# MMC-MAG.net
KiCad netlist of a schematic drawn in Altium Designer
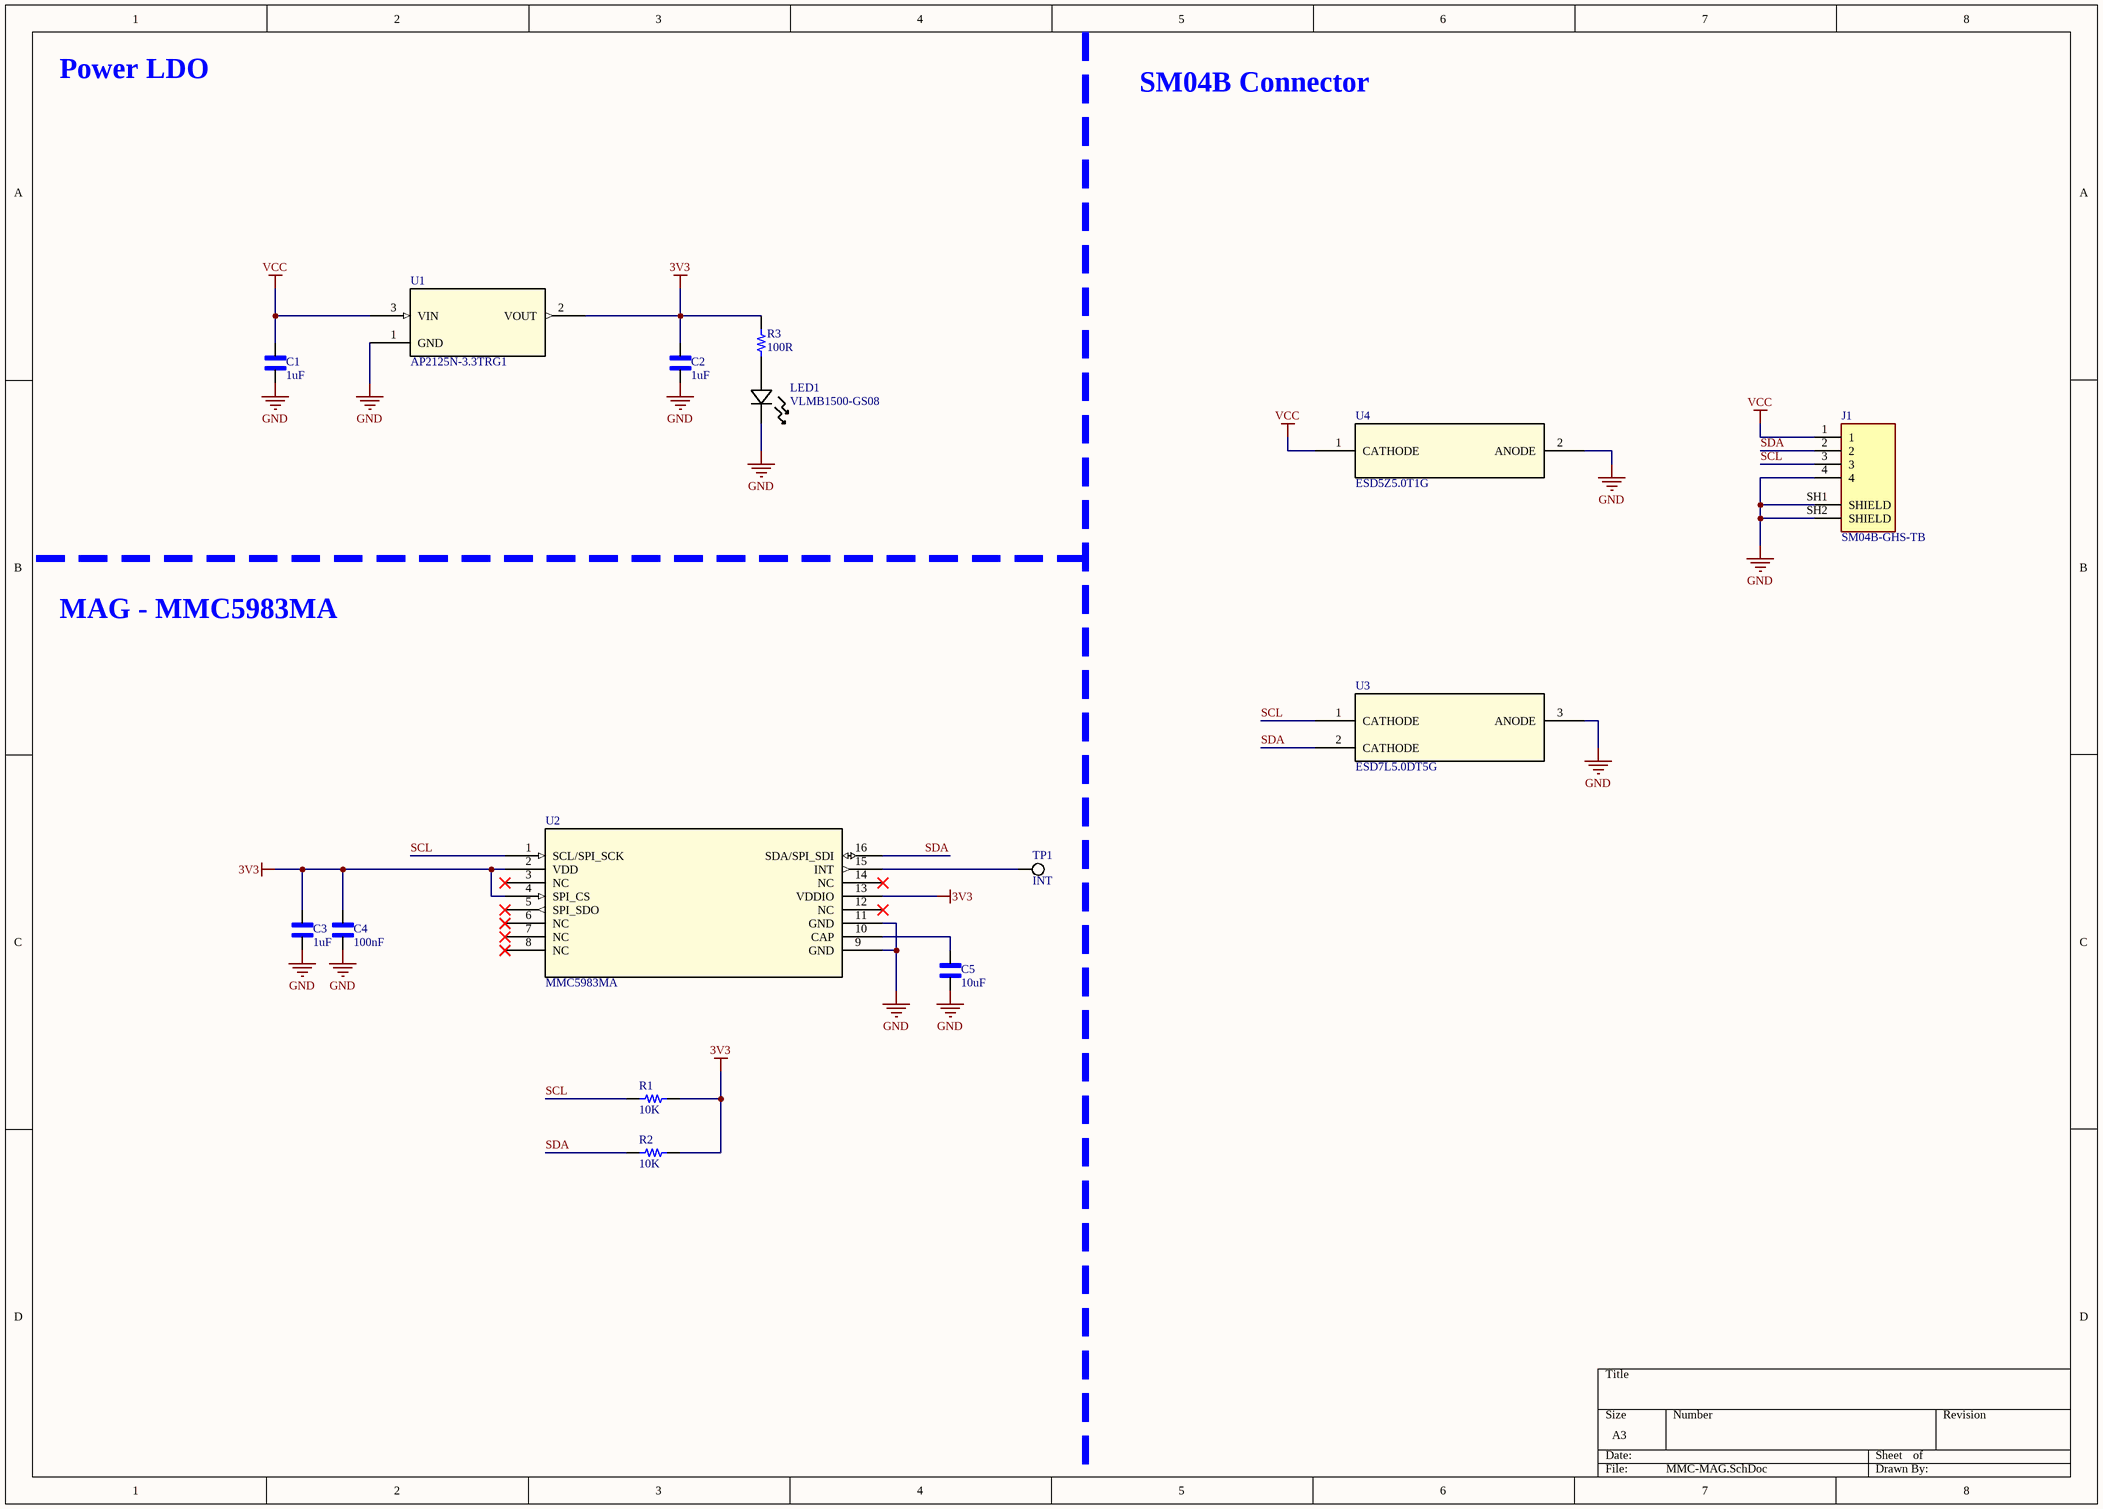
[diagram p0: MMC-MAG.SchDoc]

(export (version "E")
  (design (tool "Eeschema 10.0.6"))
  (components
    (comp (ref "C1")
      (value "1uF")
      (footprint "CAP0402")
      (description "1 ÂµF Â±10% 25V Ceramic Capacitor X5R 0402 (1005 Metric)")
      (fields (field (name "MF") "Murata") (field (name "MPN") "GRM155R61E105KA12D"))
      (libsource (lib "MAG-Schlib") (part "GRM155R61E105KA12D"))
    )
    (comp (ref "C2")
      (value "1uF")
      (footprint "CAP0402")
      (description "1 ÂµF Â±10% 25V Ceramic Capacitor X5R 0402 (1005 Metric)")
      (fields (field (name "MF") "Murata") (field (name "MPN") "GRM155R61E105KA12D"))
      (libsource (lib "MAG-Schlib") (part "GRM155R61E105KA12D"))
    )
    (comp (ref "C3")
      (value "1uF")
      (footprint "CAP0402")
      (description "1 ÂµF Â±10% 25V Ceramic Capacitor X5R 0402 (1005 Metric)")
      (fields (field (name "MF") "Murata") (field (name "MPN") "GRM155R61E105KA12D"))
      (libsource (lib "MAG-Schlib") (part "GRM155R61E105KA12D"))
    )
    (comp (ref "C4")
      (value "100nF")
      (footprint "CAP0402")
      (description "Ceramic Capacitor, Ceramic, 10V, 10% +Tol, 10% -Tol, X5R, 15% TC, 0.1uF, Surface Mount, 0402")
      (fields
        (field (name "MANUFACTURER") "Murata")
        (field (name "MANUFACTURER PART NUMBER") "GRM155R61A104KA01D")
      )
      (libsource (lib "MAG-Schlib") (part "GRM155R61A104KA01D"))
    )
    (comp (ref "C5")
      (value "10uF")
      (footprint "CAP0402")
      (description "Ceramic Capacitor, Ceramic, 10V, 20% +Tol, 20% -Tol, X5R, 15% TC, 10uF, Surface Mount, 0402")
      (fields
        (field (name "MANUFACTURER") "Murata")
        (field (name "MANUFACTURER PART NUMBER") "GRM155R61A106ME11D")
      )
      (libsource (lib "MAG-Schlib") (part "GRM155R61A106ME11D"))
    )
    (comp (ref "J1")
      (value "SM04B-GHS-TB")
      (footprint "JST_SM04B-GHS-TB(LF)(SN)-")
      (description "Connector Header Surface Mount, Right Angle 4 position 0.049 (1.25mm)")
      (fields (field (name "MF") "JST Sales America Inc.") (field (name "MPN") "SM04B-GHS-TB(LF)(SN)"))
      (libsource (lib "MAG-Schlib") (part "SM04B-GHS-TB(LF)(SN)-"))
    )
    (comp (ref "LED1")
      (value "VLMB1500-GS08")
      (footprint "LED_500-GS08_VIS")
      (description "CHIPLED(0402) BLUE ULTRABRIGHT -e4")
      (fields (field (name "COPYRIGHT") "Copyright (C) 2025 Ultra Librarian. All rights reserved."))
      (libsource (lib "MAG-Schlib") (part "VLMB1500-GS08"))
    )
    (comp (ref "R1")
      (value "10K")
      (footprint "RES 0402_1005")
      (description "Res Thick Film 0402 10K Ohm 5% 0.063W(1/16W) ±100ppm/C Pad SMD T/R")
      (fields
        (field (name "MANUFACTURER") "Yageo Group")
        (field (name "MANUFACTURER PART NUMBER") "RC0402JR-0710KL")
      )
      (libsource (lib "MAG-Schlib") (part "RC0402JR-0710KL"))
    )
    (comp (ref "R2")
      (value "10K")
      (footprint "RES 0402_1005")
      (description "Res Thick Film 0402 10K Ohm 5% 0.063W(1/16W) ±100ppm/C Pad SMD T/R")
      (fields
        (field (name "MANUFACTURER") "Yageo Group")
        (field (name "MANUFACTURER PART NUMBER") "RC0402JR-0710KL")
      )
      (libsource (lib "MAG-Schlib") (part "RC0402JR-0710KL"))
    )
    (comp (ref "R3")
      (value "100R")
      (footprint "RES 0402_1005")
      (description "Res Thick Film 0402 100 Ohm 1% 0.2W ±100ppm/°C Molded SMD SMD Paper T/R")
      (fields
        (field (name "MANUFACTURER") "Vishay")
        (field (name "MANUFACTURER PART NUMBER") "CRCW0402100RFKEDHP")
      )
      (libsource (lib "MAG-Schlib") (part "CRCW0402100RFKEDHP"))
    )
    (comp (ref "TP1")
      (value "INT")
      (footprint "TEST_POINT")
      (libsource (lib "MAG-Schlib") (part "TEST_POINT"))
    )
    (comp (ref "U1")
      (value "AP2125N-3.3TRG1")
      (footprint "SOT-23_DIO")
      (description "IC REG LINEAR 3.3V 300MA SOT23-3")
      (fields (field (name "COPYRIGHT") "Copyright (C) 2025 Ultra Librarian. All rights reserved."))
      (libsource (lib "MAG-Schlib") (part "AP2125N-3.3TRG1"))
    )
    (comp (ref "U2")
      (value "MMC5983MA")
      (footprint "MMC5983MA_MEM")
      (description "3-AXIS MAGNETIC SENSOR")
      (fields (field (name "COPYRIGHT") "Copyright (C) 2025 Ultra Librarian. All rights reserved."))
      (libsource (lib "MMC5983MA") (part "MMC5983MA"))
    )
    (comp (ref "U3")
      (value "ESD7L5.0DT5G")
      (footprint "SOT-723_0P85X1P25_ONS")
      (description "TVS DIODE 5VWM 10.4VC SOT723")
      (fields (field (name "COPYRIGHT") "Copyright (C) 2025 Ultra Librarian. All rights reserved."))
      (libsource (lib "ESD7L5P0DT5G") (part "ESD7L5.0DT5G"))
    )
    (comp (ref "U4")
      (value "ESD5Z5.0T1G")
      (footprint "SOD-523_0P9X1P3_ONS")
      (description "TVS DIODE 5VWM 18.6VC SOD523")
      (fields (field (name "COPYRIGHT") "Copyright (C) 2025 Ultra Librarian. All rights reserved."))
      (libsource (lib "MAG-Schlib") (part "ESD5Z5.0T1G"))
    )
  )
  (nets
    (net (code "1") (name "/SCL") (class "Default")
      (node (ref "J1") (pin "3") (pinfunction "3_3") (pintype "passive"))
      (node (ref "R1") (pin "1") (pinfunction "1_1") (pintype "passive"))
      (node (ref "U2") (pin "1") (pinfunction "SCL/SPI_SCK_1") (pintype "input"))
      (node (ref "U3") (pin "1") (pinfunction "CATHODE_1") (pintype "passive"))
    )
    (net (code "2") (name "/SDA") (class "Default")
      (node (ref "J1") (pin "2") (pinfunction "2_2") (pintype "passive"))
      (node (ref "R2") (pin "2") (pinfunction "2_2") (pintype "passive"))
      (node (ref "U2") (pin "16") (pinfunction "SDA/SPI_SDI_16") (pintype "bidirectional"))
      (node (ref "U3") (pin "2") (pinfunction "CATHODE_2") (pintype "passive"))
    )
    (net (code "3") (name "3V3") (class "Default")
      (node (ref "C2") (pin "2") (pinfunction "2_2") (pintype "passive"))
      (node (ref "C3") (pin "2") (pinfunction "2_2") (pintype "passive"))
      (node (ref "C4") (pin "2") (pinfunction "2_2") (pintype "passive"))
      (node (ref "R1") (pin "2") (pinfunction "2_2") (pintype "passive"))
      (node (ref "R2") (pin "1") (pinfunction "1_1") (pintype "passive"))
      (node (ref "R3") (pin "2") (pinfunction "2_2") (pintype "passive"))
      (node (ref "U1") (pin "2") (pinfunction "VOUT_2") (pintype "output"))
      (node (ref "U2") (pin "13") (pinfunction "VDDIO_13") (pintype "power_in"))
      (node (ref "U2") (pin "2") (pinfunction "VDD_2") (pintype "power_in"))
      (node (ref "U2") (pin "4") (pinfunction "SPI_CS_4") (pintype "input"))
    )
    (net (code "4") (name "GND") (class "Default")
      (node (ref "C1") (pin "1") (pinfunction "1_1") (pintype "passive"))
      (node (ref "C2") (pin "1") (pinfunction "1_1") (pintype "passive"))
      (node (ref "C3") (pin "1") (pinfunction "1_1") (pintype "passive"))
      (node (ref "C4") (pin "1") (pinfunction "1_1") (pintype "passive"))
      (node (ref "C5") (pin "1") (pinfunction "1_1") (pintype "passive"))
      (node (ref "J1") (pin "4") (pinfunction "4_4") (pintype "passive"))
      (node (ref "J1") (pin "SH1") (pinfunction "SHIELD_SH1") (pintype "power_in"))
      (node (ref "J1") (pin "SH2") (pinfunction "SHIELD_SH2") (pintype "power_in"))
      (node (ref "LED1") (pin "1") (pinfunction "1_1") (pintype "passive"))
      (node (ref "U1") (pin "1") (pinfunction "GND_1") (pintype "power_in"))
      (node (ref "U2") (pin "11") (pinfunction "GND_11") (pintype "power_in"))
      (node (ref "U2") (pin "9") (pinfunction "GND_9") (pintype "power_in"))
      (node (ref "U3") (pin "3") (pinfunction "ANODE_3") (pintype "passive"))
      (node (ref "U4") (pin "2") (pinfunction "ANODE_2") (pintype "passive"))
    )
    (net (code "5") (name "Net-(LED1-Pad2)") (class "Default")
      (node (ref "LED1") (pin "2") (pinfunction "2_2") (pintype "passive"))
      (node (ref "R3") (pin "1") (pinfunction "1_1") (pintype "passive"))
    )
    (net (code "6") (name "Net-(U2-CAP)") (class "Default")
      (node (ref "C5") (pin "2") (pinfunction "2_2") (pintype "passive"))
      (node (ref "U2") (pin "10") (pinfunction "CAP_10") (pintype "power_in"))
    )
    (net (code "7") (name "Net-(U2-INT)") (class "Default")
      (node (ref "TP1") (pin "1") (pinfunction "1_1") (pintype "passive"))
      (node (ref "U2") (pin "15") (pinfunction "INT_15") (pintype "output"))
    )
    (net (code "8") (name "VCC") (class "Default")
      (node (ref "C1") (pin "2") (pinfunction "2_2") (pintype "passive"))
      (node (ref "J1") (pin "1") (pinfunction "1_1") (pintype "passive"))
      (node (ref "U1") (pin "3") (pinfunction "VIN_3") (pintype "input"))
      (node (ref "U4") (pin "1") (pinfunction "CATHODE_1") (pintype "passive"))
    )
    (net (code "9") (name "unconnected-(U2-NC-Pad3)") (class "Default")
      (node (ref "U2") (pin "3") (pinfunction "NC_3") (pintype "passive+no_connect"))
    )
    (net (code "10") (name "unconnected-(U2-NC-Pad6)") (class "Default")
      (node (ref "U2") (pin "6") (pinfunction "NC_6") (pintype "passive+no_connect"))
    )
    (net (code "11") (name "unconnected-(U2-NC-Pad7)") (class "Default")
      (node (ref "U2") (pin "7") (pinfunction "NC_7") (pintype "passive+no_connect"))
    )
    (net (code "12") (name "unconnected-(U2-NC-Pad8)") (class "Default")
      (node (ref "U2") (pin "8") (pinfunction "NC_8") (pintype "passive+no_connect"))
    )
    (net (code "13") (name "unconnected-(U2-NC-Pad12)") (class "Default")
      (node (ref "U2") (pin "12") (pinfunction "NC_12") (pintype "passive+no_connect"))
    )
    (net (code "14") (name "unconnected-(U2-NC-Pad14)") (class "Default")
      (node (ref "U2") (pin "14") (pinfunction "NC_14") (pintype "passive+no_connect"))
    )
    (net (code "15") (name "unconnected-(U2-SPI_SDO-Pad5)") (class "Default")
      (node (ref "U2") (pin "5") (pinfunction "SPI_SDO_5") (pintype "output+no_connect"))
    )
  )
)
